# 555TIMER-ASTABLE-MODE.net
KiCad netlist of a schematic drawn in Altium Designer
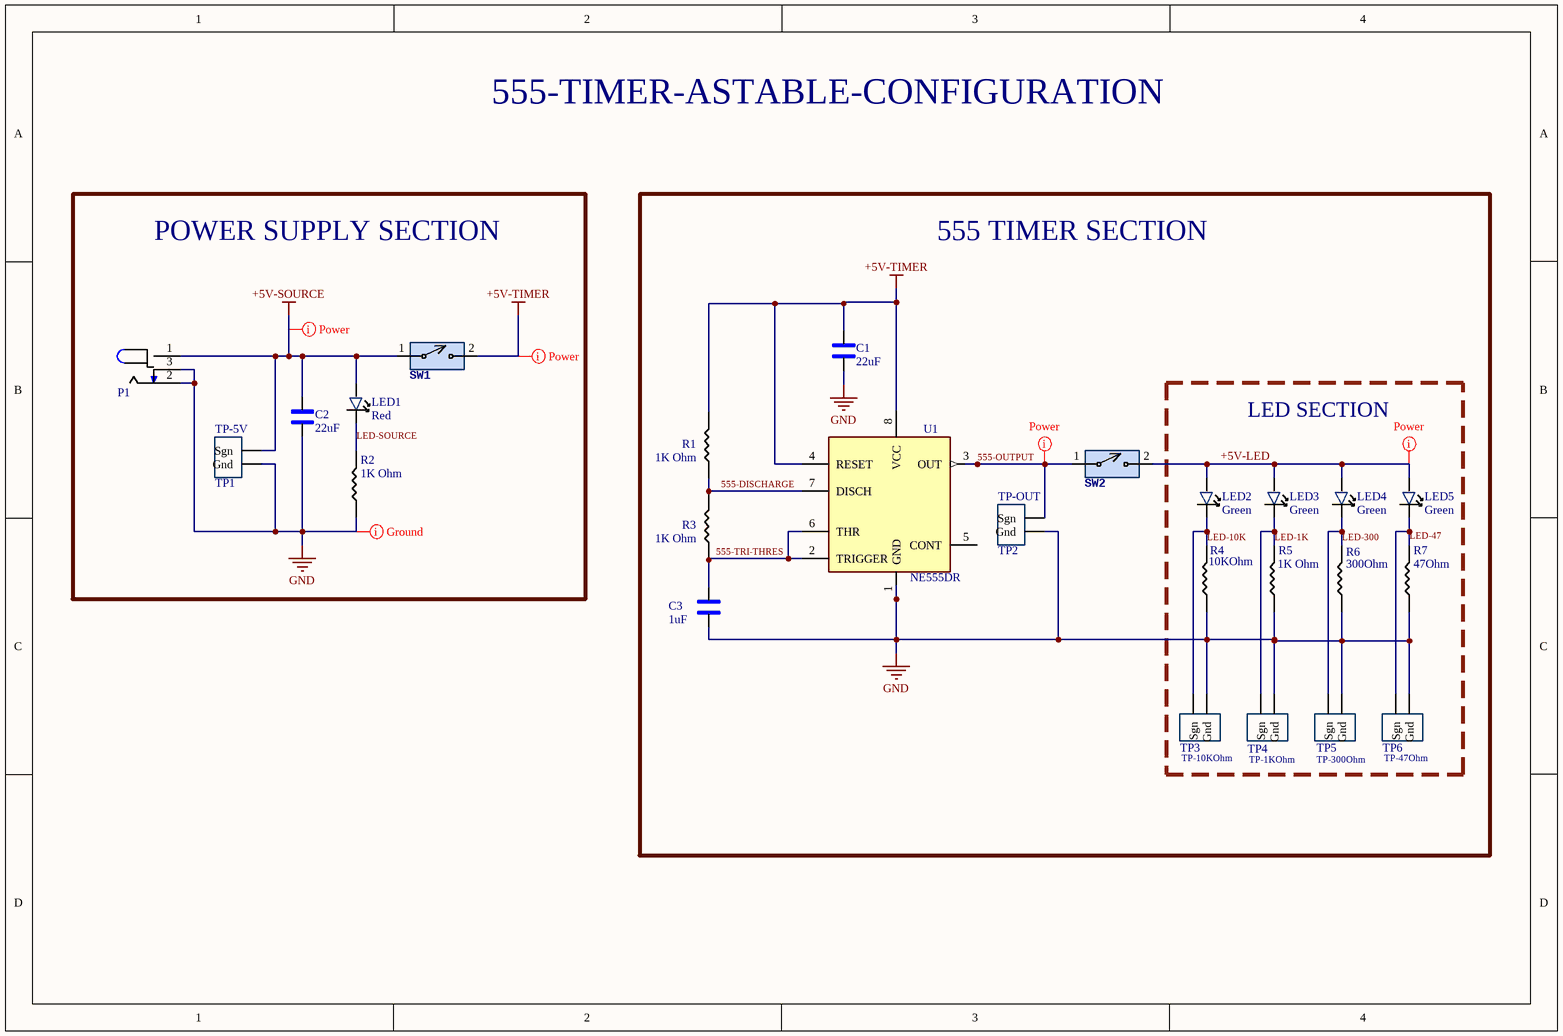
[diagram p0: 555TIMER-ASTABLE-MODE.SchDoc]

(export (version "E")
  (design (tool "Eeschema 10.0.6"))
  (components
    (comp (ref "C1")
      (value "22uF")
      (footprint "1206_Passive_Capacitor")
      (description "22uF ±10% 25V X5R 1206 Multilayer Ceramic Capacitors MLCC - SMD/SMT RoHS")
      (fields (field (name "MFR PART #") "CL31A226KAHNNNE") (field (name "LCSC PART#") "C12891"))
      (libsource (lib "ECEN5730Lib_2023_05_DS (1)") (part "C_22uF_1206"))
    )
    (comp (ref "C2")
      (value "22uF")
      (footprint "1206_Passive_Capacitor")
      (description "22uF ±10% 25V X5R 1206 Multilayer Ceramic Capacitors MLCC - SMD/SMT RoHS")
      (fields (field (name "MFR PART #") "CL31A226KAHNNNE") (field (name "LCSC PART#") "C12891"))
      (libsource (lib "ECEN5730Lib_2023_05_DS (1)") (part "C_22uF_1206"))
    )
    (comp (ref "C3")
      (value "1uF")
      (footprint "1206_Passive_Capacitor")
      (description "MULTILAYER CERAMIC CAPACITORS MLCC - SMD/SMT 1UF 50V 1206 ROHS")
      (fields (field (name "MFR PART #") "CL31B105KBHNNNE") (field (name "LCSC PART#") "C1848"))
      (libsource (lib "ECEN5730Lib_2023_05_DS (1)") (part "C_1uF_1206"))
    )
    (comp (ref "LED1")
      (value "Red")
      (footprint "LED_1206")
      (description "Red 621~631nm 1206 Light Emitting Diodes (LED) RoHS")
      (fields (field (name "MFR PART #") "15-21/R6C-FQ1R1B/2T") (field (name "LCSC PART#") "C93133"))
      (libsource (lib "ECEN5730Lib_2023_05_DS (1)") (part "LED_RED_1206"))
    )
    (comp (ref "LED2")
      (value "Green")
      (footprint "LED_1206")
      (description "Green 513~528nm 1206 Light Emitting Diodes (LED) RoHS")
      (fields (field (name "MFR PART #") "SZYY1206G") (field (name "LCSC PART#") "C434439"))
      (libsource (lib "ECEN5730Lib_2023_05_DS (1)") (part "LED_GREEN_1206"))
    )
    (comp (ref "LED3")
      (value "Green")
      (footprint "LED_1206")
      (description "Green 513~528nm 1206 Light Emitting Diodes (LED) RoHS")
      (fields (field (name "MFR PART #") "SZYY1206G") (field (name "LCSC PART#") "C434439"))
      (libsource (lib "ECEN5730Lib_2023_05_DS (1)") (part "LED_GREEN_1206"))
    )
    (comp (ref "LED4")
      (value "Green")
      (footprint "LED_1206")
      (description "Green 513~528nm 1206 Light Emitting Diodes (LED) RoHS")
      (fields (field (name "MFR PART #") "SZYY1206G") (field (name "LCSC PART#") "C434439"))
      (libsource (lib "ECEN5730Lib_2023_05_DS (1)") (part "LED_GREEN_1206"))
    )
    (comp (ref "LED5")
      (value "Green")
      (footprint "LED_1206")
      (description "Green 513~528nm 1206 Light Emitting Diodes (LED) RoHS")
      (fields (field (name "MFR PART #") "SZYY1206G") (field (name "LCSC PART#") "C434439"))
      (libsource (lib "ECEN5730Lib_2023_05_DS (1)") (part "LED_GREEN_1206"))
    )
    (comp (ref "P1")
      (value "Power Jack")
      (footprint "Power_Jack")
      (description "Power Barrel Connector Jack 2.10mm ID (0.083\"), 5.50mm OD (0.217\") Through Hole, Right Angle")
      (fields (field (name "MFR PART #") "PJ-102A") (field (name "LCSC PART#") "C136744"))
      (libsource (lib "ECEN5730Lib_2023_05_DS (1)") (part "P_Power Jack"))
    )
    (comp (ref "R1")
      (value "1K Ohm")
      (footprint "1206_Passive_Resitor")
      (description "CHIP RESISTOR - SURFACE MOUNT 1KOHMS ±1% 1/4W 1206 ROHS")
      (fields (field (name "MFR PART #") "RNCP1206FTD1K00CT") (field (name "LCSC PART#") "C4410"))
      (libsource (lib "ECEN5730Lib_2023_05_DS (1)") (part "R_1K_1206"))
    )
    (comp (ref "R2")
      (value "1K Ohm")
      (footprint "1206_Passive_Resitor")
      (description "CHIP RESISTOR - SURFACE MOUNT 1KOHMS ±1% 1/4W 1206 ROHS")
      (fields (field (name "MFR PART #") "RNCP1206FTD1K00CT") (field (name "LCSC PART#") "C4410"))
      (libsource (lib "ECEN5730Lib_2023_05_DS (1)") (part "R_1K_1206"))
    )
    (comp (ref "R3")
      (value "1K Ohm")
      (footprint "1206_Passive_Resitor")
      (description "CHIP RESISTOR - SURFACE MOUNT 1KOHMS ±1% 1/4W 1206 ROHS")
      (fields (field (name "MFR PART #") "RNCP1206FTD1K00CT") (field (name "LCSC PART#") "C4410"))
      (libsource (lib "ECEN5730Lib_2023_05_DS (1)") (part "R_1K_1206"))
    )
    (comp (ref "R4")
      (value "10KOhm")
      (footprint "1206_Passive_Resitor")
      (description "10 kOhms ±5% 0.25W, 1/4W Chip Resistor 1206 (3216 Metric) Automotive AEC-Q200 Thick Film")
      (fields (field (name "MFR PART #") "RMCF1206FT10K0") (field (name "LCSC PART#") "C17902"))
      (libsource (lib "ECEN5730Lib_2023_05_DS (1)") (part "R_10KOhm_1206"))
    )
    (comp (ref "R5")
      (value "1K Ohm")
      (footprint "1206_Passive_Resitor")
      (description "CHIP RESISTOR - SURFACE MOUNT 1KOHMS ±1% 1/4W 1206 ROHS")
      (fields (field (name "MFR PART #") "RNCP1206FTD1K00CT") (field (name "LCSC PART#") "C4410"))
      (libsource (lib "ECEN5730Lib_2023_05_DS (1)") (part "R_1K_1206"))
    )
    (comp (ref "R6")
      (value "300Ohm")
      (footprint "1206_Passive_Resitor")
      (description "CHIP RESISTOR - SURFACE MOUNT 300OHMS ±1% 1/4W 1206 ROHS")
      (fields (field (name "MFR PART #") "1206W4F3000T5E") (field (name "LCSC PART#") "C17887"))
      (libsource (lib "ECEN5730Lib_2023_05_DS (1)") (part "R_300Ohm_1206"))
    )
    (comp (ref "R7")
      (value "47Ohm")
      (footprint "1206_Passive_Resitor")
      (description "47Ω ±5% 0.25W ±200ppm/℃ 1206 Chip Resistor - Surface Mount RoHS")
      (fields (field (name "MFR PART #") "1206W4J0470T5E") (field (name "LCSC PART#") "C25384"))
      (libsource (lib "ECEN5730Lib_2023_05_DS (1)") (part "R_47Ohm_1206"))
    )
    (comp (ref "SW1")
      (value "SW_2Pin_100mil_Switch")
      (footprint "2Pin-Header-Conn")
      (description "2Pin Header")
      (fields (field (name "LCSC PART#") "C124375"))
      (libsource (lib "ECEN5730Lib_2023_05_DS (1)") (part "SW_2Pin_100mil_Switch"))
    )
    (comp (ref "SW2")
      (value "SW_2Pin_100mil_Switch")
      (footprint "2Pin-Header-Conn")
      (description "2Pin Header")
      (fields (field (name "LCSC PART#") "C124375"))
      (libsource (lib "ECEN5730Lib_2023_05_DS (1)") (part "SW_2Pin_100mil_Switch"))
    )
    (comp (ref "TP1")
      (value "TP-5V")
      (footprint "TP10x_Probe")
      (description "Test Point 300 mil centers")
      (libsource (lib "ECEN5730Lib_2023_05_DS (1)") (part "TP_10x_Probe"))
    )
    (comp (ref "TP2")
      (value "TP-OUT")
      (footprint "TP10x_Probe")
      (description "Test Point 300 mil centers")
      (libsource (lib "ECEN5730Lib_2023_05_DS (1)") (part "TP_10x_Probe"))
    )
    (comp (ref "TP3")
      (value "TP-10KOhm")
      (footprint "TP10x_Probe")
      (description "Test Point 300 mil centers")
      (libsource (lib "") (part "TP_10x_Probe_1"))
    )
    (comp (ref "TP4")
      (value "TP-1KOhm")
      (footprint "TP10x_Probe")
      (description "Test Point 300 mil centers")
      (libsource (lib "") (part "TP_10x_Probe_1"))
    )
    (comp (ref "TP5")
      (value "TP-300Ohm")
      (footprint "TP10x_Probe")
      (description "Test Point 300 mil centers")
      (libsource (lib "") (part "TP_10x_Probe_1"))
    )
    (comp (ref "TP6")
      (value "TP-47Ohm")
      (footprint "TP10x_Probe")
      (description "Test Point 300 mil centers")
      (libsource (lib "") (part "TP_10x_Probe_1"))
    )
    (comp (ref "U1")
      (value "NE555DR")
      (footprint "TS555IDTTR")
      (description "555 Timer SOIC-8_150MIL ROHS 150ns Rise Time")
      (fields (field (name "LCSC PART#") "C7593"))
      (libsource (lib "ECEN5730Lib_2023_05_DS (1)") (part "U_555_Slow"))
    )
  )
  (nets
    (net (code "1") (name "+5V-SOURCE") (class "Default")
      (node (ref "C2") (pin "2") (pinfunction "2_2") (pintype "passive"))
      (node (ref "LED1") (pin "1") (pinfunction "1_1") (pintype "passive"))
      (node (ref "P1") (pin "1") (pinfunction "1_1") (pintype "power_in"))
      (node (ref "SW1") (pin "1") (pinfunction "1_1") (pintype "passive"))
      (node (ref "TP1") (pin "1") (pinfunction "Sgn_1") (pintype "passive"))
    )
    (net (code "2") (name "+5V-TIMER") (class "Default")
      (node (ref "C1") (pin "2") (pinfunction "2_2") (pintype "passive"))
      (node (ref "R1") (pin "2") (pinfunction "2_2") (pintype "passive"))
      (node (ref "SW1") (pin "2") (pinfunction "2_2") (pintype "passive"))
      (node (ref "U1") (pin "4") (pinfunction "RESET_4") (pintype "passive"))
      (node (ref "U1") (pin "8") (pinfunction "VCC_8") (pintype "power_in"))
    )
    (net (code "3") (name "/+5V-LED") (class "Default")
      (node (ref "LED2") (pin "1") (pinfunction "1_1") (pintype "passive"))
      (node (ref "LED3") (pin "1") (pinfunction "1_1") (pintype "passive"))
      (node (ref "LED4") (pin "1") (pinfunction "1_1") (pintype "passive"))
      (node (ref "LED5") (pin "1") (pinfunction "1_1") (pintype "passive"))
      (node (ref "SW2") (pin "2") (pinfunction "2_2") (pintype "passive"))
    )
    (net (code "4") (name "/555-DISCHARGE") (class "Default")
      (node (ref "R1") (pin "1") (pinfunction "1_1") (pintype "passive"))
      (node (ref "R3") (pin "2") (pinfunction "2_2") (pintype "passive"))
      (node (ref "U1") (pin "7") (pinfunction "DISCH_7") (pintype "passive"))
    )
    (net (code "5") (name "/555-OUTPUT") (class "Default")
      (node (ref "SW2") (pin "1") (pinfunction "1_1") (pintype "passive"))
      (node (ref "TP2") (pin "1") (pinfunction "Sgn_1") (pintype "passive"))
      (node (ref "U1") (pin "3") (pinfunction "OUT_3") (pintype "output"))
    )
    (net (code "6") (name "/555-TRI-THRES") (class "Default")
      (node (ref "C3") (pin "2") (pinfunction "2_2") (pintype "passive"))
      (node (ref "R3") (pin "1") (pinfunction "1_1") (pintype "passive"))
      (node (ref "U1") (pin "2") (pinfunction "TRIGGER_2") (pintype "passive"))
      (node (ref "U1") (pin "6") (pinfunction "THR_6") (pintype "passive"))
    )
    (net (code "7") (name "/LED-1K") (class "Default")
      (node (ref "LED3") (pin "2") (pinfunction "2_2") (pintype "passive"))
      (node (ref "R5") (pin "2") (pinfunction "2_2") (pintype "passive"))
      (node (ref "TP4") (pin "1") (pinfunction "Sgn_1") (pintype "passive"))
    )
    (net (code "8") (name "/LED-10K") (class "Default")
      (node (ref "LED2") (pin "2") (pinfunction "2_2") (pintype "passive"))
      (node (ref "R4") (pin "2") (pinfunction "2_2") (pintype "passive"))
      (node (ref "TP3") (pin "1") (pinfunction "Sgn_1") (pintype "passive"))
    )
    (net (code "9") (name "/LED-47") (class "Default")
      (node (ref "LED5") (pin "2") (pinfunction "2_2") (pintype "passive"))
      (node (ref "R7") (pin "2") (pinfunction "2_2") (pintype "passive"))
      (node (ref "TP6") (pin "1") (pinfunction "Sgn_1") (pintype "passive"))
    )
    (net (code "10") (name "/LED-300") (class "Default")
      (node (ref "LED4") (pin "2") (pinfunction "2_2") (pintype "passive"))
      (node (ref "R6") (pin "2") (pinfunction "2_2") (pintype "passive"))
      (node (ref "TP5") (pin "1") (pinfunction "Sgn_1") (pintype "passive"))
    )
    (net (code "11") (name "/LED-SOURCE") (class "Default")
      (node (ref "LED1") (pin "2") (pinfunction "2_2") (pintype "passive"))
      (node (ref "R2") (pin "2") (pinfunction "2_2") (pintype "passive"))
    )
    (net (code "12") (name "GND") (class "Default")
      (node (ref "C1") (pin "1") (pinfunction "1_1") (pintype "passive"))
      (node (ref "C2") (pin "1") (pinfunction "1_1") (pintype "passive"))
      (node (ref "C3") (pin "1") (pinfunction "1_1") (pintype "passive"))
      (node (ref "P1") (pin "2") (pinfunction "2_2") (pintype "power_in"))
      (node (ref "P1") (pin "3") (pinfunction "3_3") (pintype "power_in"))
      (node (ref "R2") (pin "1") (pinfunction "1_1") (pintype "passive"))
      (node (ref "R4") (pin "1") (pinfunction "1_1") (pintype "passive"))
      (node (ref "R5") (pin "1") (pinfunction "1_1") (pintype "passive"))
      (node (ref "R6") (pin "1") (pinfunction "1_1") (pintype "passive"))
      (node (ref "R7") (pin "1") (pinfunction "1_1") (pintype "passive"))
      (node (ref "TP1") (pin "2") (pinfunction "Gnd_2") (pintype "passive"))
      (node (ref "TP2") (pin "2") (pinfunction "Gnd_2") (pintype "passive"))
      (node (ref "TP3") (pin "2") (pinfunction "Gnd_2") (pintype "passive"))
      (node (ref "TP4") (pin "2") (pinfunction "Gnd_2") (pintype "passive"))
      (node (ref "TP5") (pin "2") (pinfunction "Gnd_2") (pintype "passive"))
      (node (ref "TP6") (pin "2") (pinfunction "Gnd_2") (pintype "passive"))
      (node (ref "U1") (pin "1") (pinfunction "GND_1") (pintype "power_in"))
    )
    (net (code "13") (name "unconnected-(U1-CONT-Pad5)") (class "Default")
      (node (ref "U1") (pin "5") (pinfunction "CONT_5") (pintype "passive"))
    )
  )
)
